# sch.net
KiCad netlist of a schematic drawn in EasyEDA
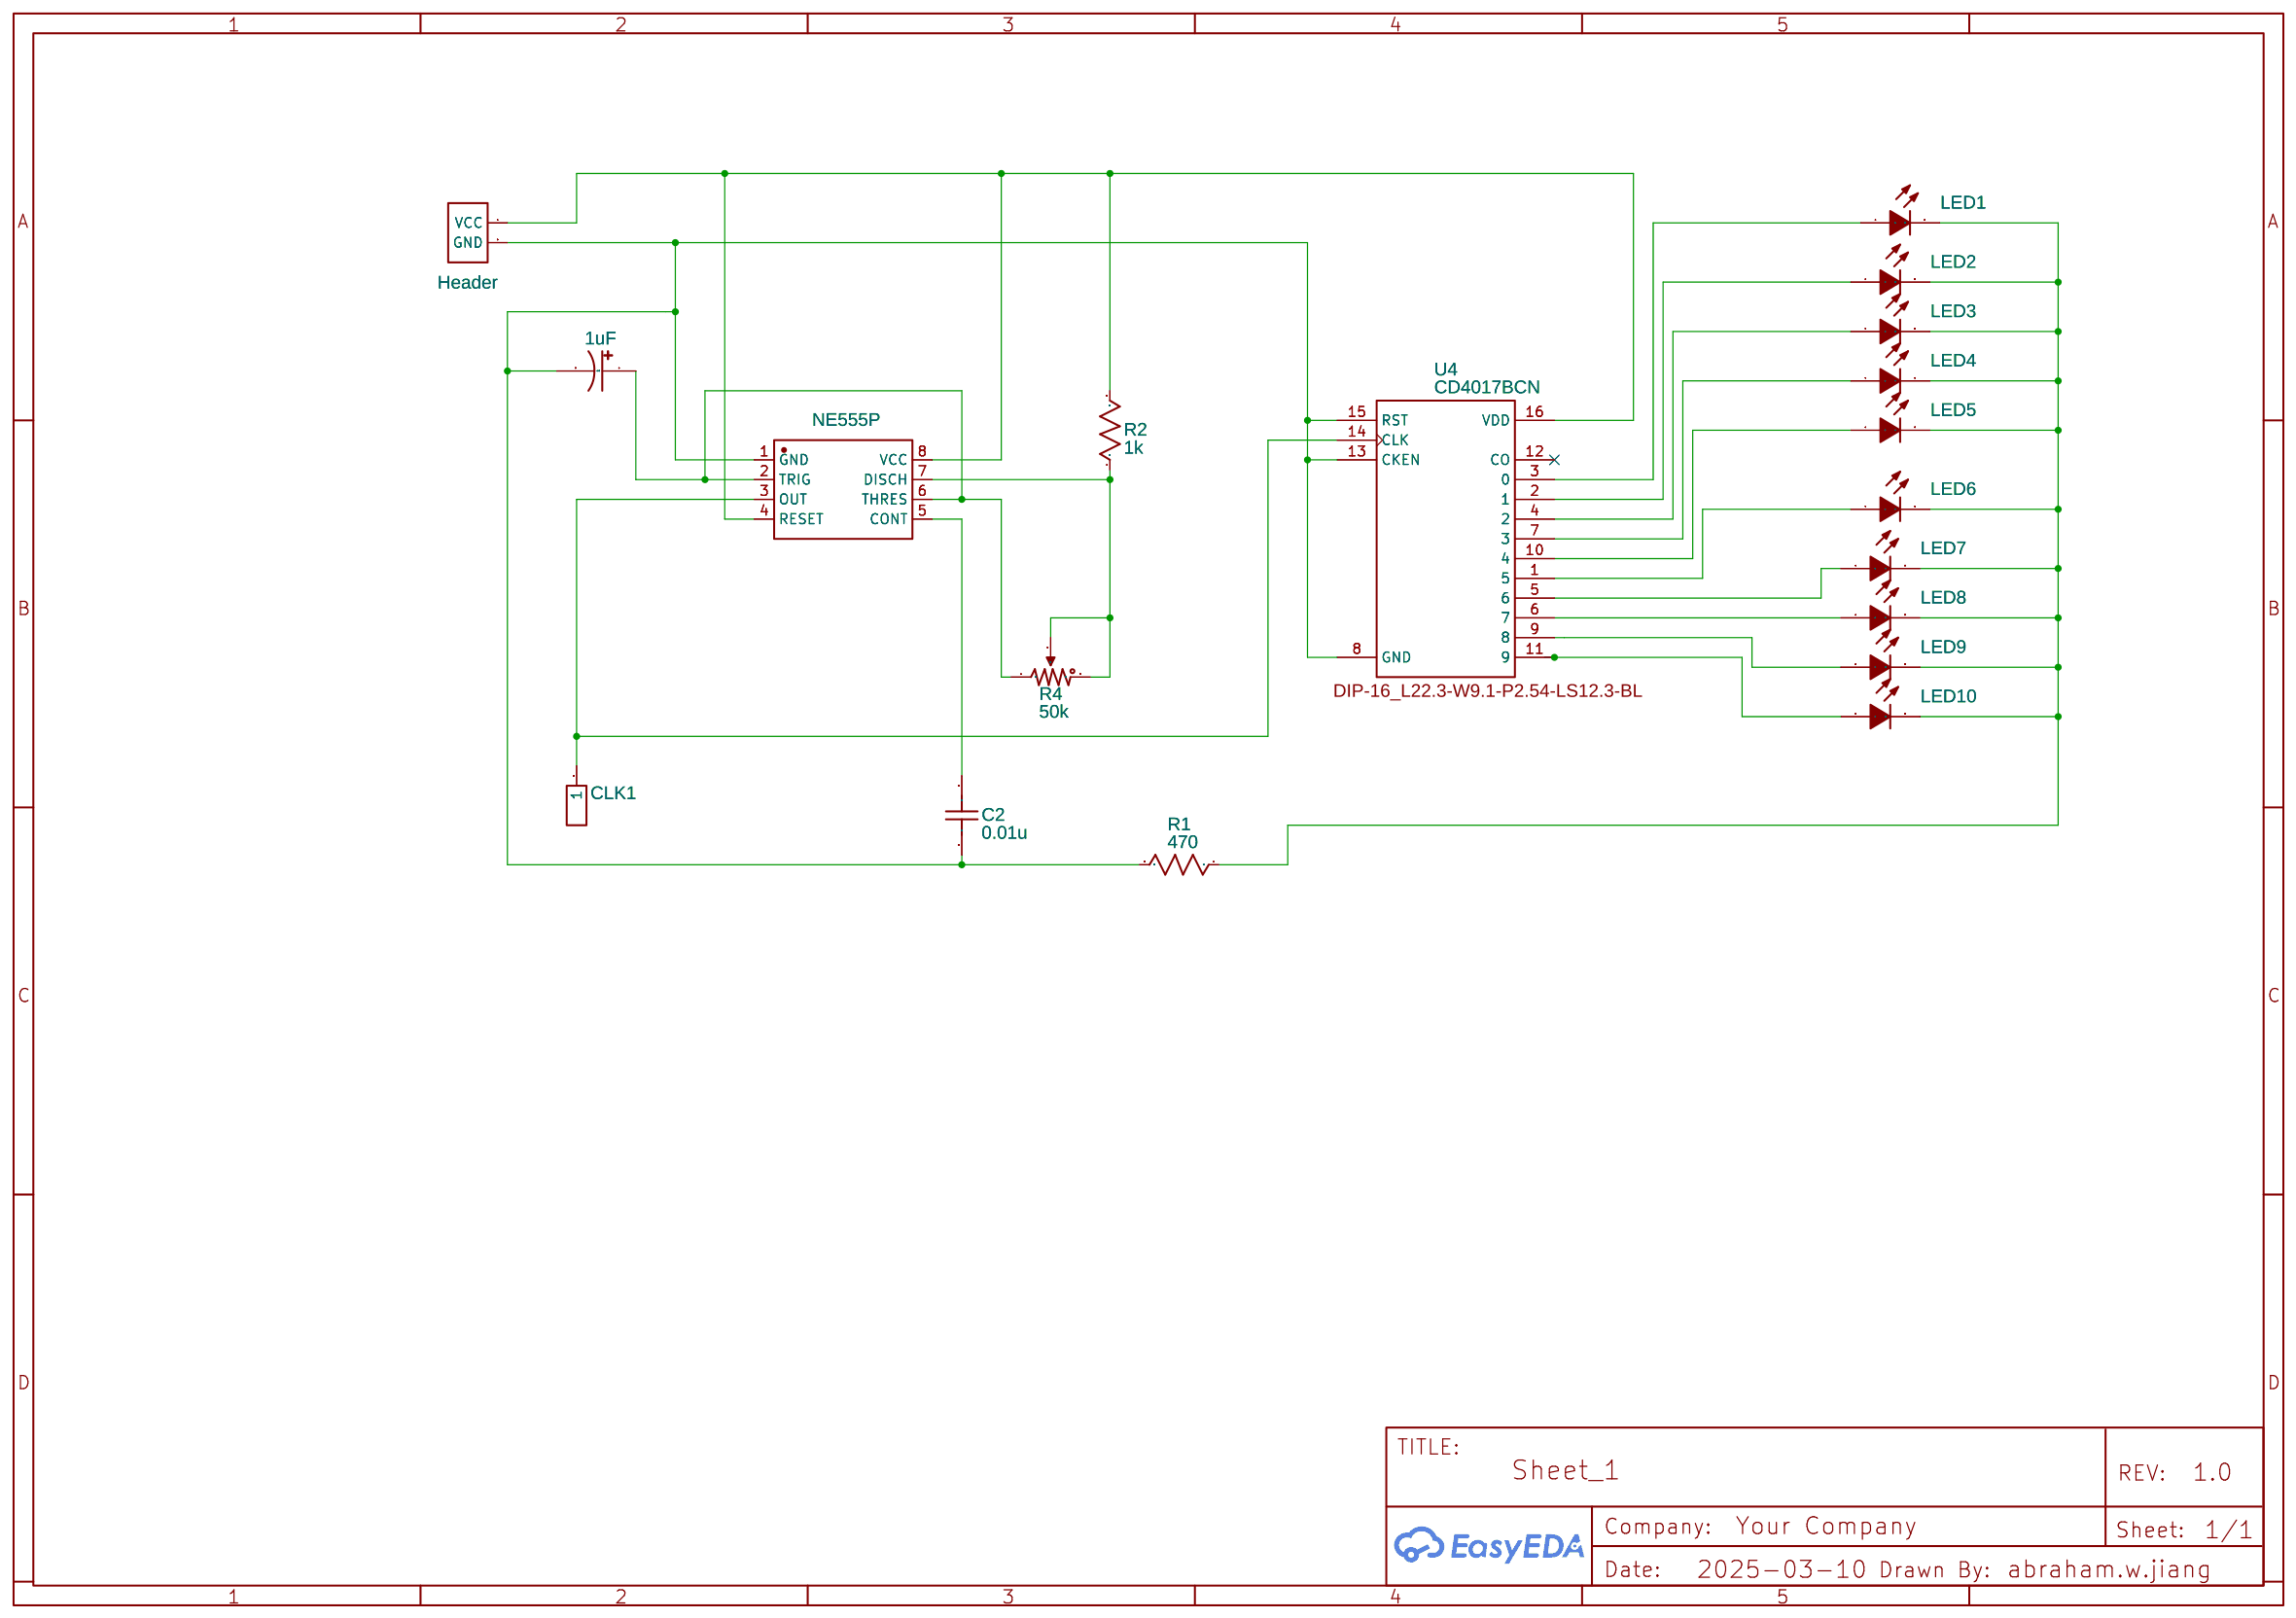
[diagram p0: schematic sheet]

(export (version "E")
  (design (tool "Eeschema 10.0.6"))
  (components
    (comp (ref "C1")
      (value "1uF")
      (fields (field (name "Manufacturer Part") "UVZ1H010MDD") (field (name "Manufacturer") "Nichicon(尼吉康)"))
      (libsource (lib "") (part "UVZ1H010MDD"))
    )
    (comp (ref "C2") (value "0.01u") (libsource (lib "") (part "C_0603_US")))
    (comp (ref "CLK1")
      (value "C81276")
      (fields
        (field (name "Manufacturer Part") "2.54-1*1P针")
        (field (name "Manufacturer") "BOOMELE(Boom Precision Elec)")
      )
      (libsource (lib "") (part "Header-Male-2.54_1x1"))
    )
    (comp (ref "H1") (value "Header") (libsource (lib "") (part "HEADER-FEMALE-2.54_1X2")))
    (comp (ref "LED1") (value "LED_5MM") (libsource (lib "") (part "LED_5MM")))
    (comp (ref "LED2") (value "LED_5MM") (libsource (lib "") (part "LED_5MM")))
    (comp (ref "LED3") (value "LED_5MM") (libsource (lib "") (part "LED_5MM")))
    (comp (ref "LED4") (value "LED_5MM") (libsource (lib "") (part "LED_5MM")))
    (comp (ref "LED5") (value "LED_5MM") (libsource (lib "") (part "LED_5MM")))
    (comp (ref "LED6") (value "LED_5MM") (libsource (lib "") (part "LED_5MM")))
    (comp (ref "LED7") (value "LED_5MM") (libsource (lib "") (part "LED_5MM")))
    (comp (ref "LED8") (value "LED_5MM") (libsource (lib "") (part "LED_5MM")))
    (comp (ref "LED9") (value "LED_5MM") (libsource (lib "") (part "LED_5MM")))
    (comp (ref "LED10") (value "LED_5MM") (libsource (lib "") (part "LED_5MM")))
    (comp (ref "R1")
      (value "470")
      (fields (field (name "Manufacturer Part") "?"))
      (libsource (lib "") (part "Resistor"))
    )
    (comp (ref "R2")
      (value "1k")
      (fields (field (name "Manufacturer Part") "?"))
      (libsource (lib "") (part "Resistor_1"))
    )
    (comp (ref "R4")
      (value "50k")
      (fields (field (name "Manufacturer Part") "?"))
      (libsource (lib "") (part "Potentiometer"))
    )
    (comp (ref "U2")
      (value "NE555P")
      (fields (field (name "Manufacturer") "TI(德州仪器)"))
      (libsource (lib "") (part "NE555P"))
    )
    (comp (ref "U4") (value "CD4017BCN") (libsource (lib "") (part "CD4017BCN")))
  )
  (nets
    (net (code "1") (name "Net-(H1-GND)") (class "Default")
      (node (ref "C1") (pin "2") (pinfunction "2_2") (pintype "unspecified"))
      (node (ref "C2") (pin "2") (pinfunction "2_2") (pintype "unspecified"))
      (node (ref "H1") (pin "2") (pinfunction "GND_2") (pintype "unspecified"))
      (node (ref "R1") (pin "2") (pinfunction "2_2") (pintype "unspecified"))
      (node (ref "U2") (pin "1") (pinfunction "GND_1") (pintype "unspecified"))
      (node (ref "U4") (pin "13") (pinfunction "CKEN_13") (pintype "unspecified"))
      (node (ref "U4") (pin "15") (pinfunction "RST_15") (pintype "unspecified"))
      (node (ref "U4") (pin "8") (pinfunction "GND_8") (pintype "passive"))
    )
    (net (code "2") (name "Net-(H1-VCC)") (class "Default")
      (node (ref "H1") (pin "1") (pinfunction "VCC_1") (pintype "unspecified"))
      (node (ref "R2") (pin "2") (pinfunction "2_2") (pintype "unspecified"))
      (node (ref "U2") (pin "4") (pinfunction "RESET_4") (pintype "unspecified"))
      (node (ref "U2") (pin "8") (pinfunction "VCC_8") (pintype "unspecified"))
      (node (ref "U4") (pin "16") (pinfunction "VDD_16") (pintype "passive"))
    )
    (net (code "3") (name "Net-(LED1-A)") (class "Default")
      (node (ref "LED1") (pin "1") (pinfunction "A_1") (pintype "input"))
      (node (ref "U4") (pin "3") (pinfunction "0_3") (pintype "output"))
    )
    (net (code "4") (name "Net-(LED1-K)") (class "Default")
      (node (ref "LED1") (pin "2") (pinfunction "K_2") (pintype "input"))
      (node (ref "LED10") (pin "2") (pinfunction "K_2") (pintype "input"))
      (node (ref "LED2") (pin "2") (pinfunction "K_2") (pintype "input"))
      (node (ref "LED3") (pin "2") (pinfunction "K_2") (pintype "input"))
      (node (ref "LED4") (pin "2") (pinfunction "K_2") (pintype "input"))
      (node (ref "LED5") (pin "2") (pinfunction "K_2") (pintype "input"))
      (node (ref "LED6") (pin "2") (pinfunction "K_2") (pintype "input"))
      (node (ref "LED7") (pin "2") (pinfunction "K_2") (pintype "input"))
      (node (ref "LED8") (pin "2") (pinfunction "K_2") (pintype "input"))
      (node (ref "LED9") (pin "2") (pinfunction "K_2") (pintype "input"))
      (node (ref "R1") (pin "1") (pinfunction "1_1") (pintype "unspecified"))
    )
    (net (code "5") (name "Net-(LED2-A)") (class "Default")
      (node (ref "LED2") (pin "1") (pinfunction "A_1") (pintype "input"))
      (node (ref "U4") (pin "2") (pinfunction "1_2") (pintype "output"))
    )
    (net (code "6") (name "Net-(LED3-A)") (class "Default")
      (node (ref "LED3") (pin "1") (pinfunction "A_1") (pintype "input"))
      (node (ref "U4") (pin "4") (pinfunction "2_4") (pintype "output"))
    )
    (net (code "7") (name "Net-(LED4-A)") (class "Default")
      (node (ref "LED4") (pin "1") (pinfunction "A_1") (pintype "input"))
      (node (ref "U4") (pin "7") (pinfunction "3_7") (pintype "output"))
    )
    (net (code "8") (name "Net-(LED5-A)") (class "Default")
      (node (ref "LED5") (pin "1") (pinfunction "A_1") (pintype "input"))
      (node (ref "U4") (pin "10") (pinfunction "4_10") (pintype "output"))
    )
    (net (code "9") (name "Net-(LED6-A)") (class "Default")
      (node (ref "LED6") (pin "1") (pinfunction "A_1") (pintype "input"))
      (node (ref "U4") (pin "1") (pinfunction "5_1") (pintype "output"))
    )
    (net (code "10") (name "Net-(LED7-A)") (class "Default")
      (node (ref "LED7") (pin "1") (pinfunction "A_1") (pintype "input"))
      (node (ref "U4") (pin "5") (pinfunction "6_5") (pintype "output"))
    )
    (net (code "11") (name "Net-(LED8-A)") (class "Default")
      (node (ref "LED8") (pin "1") (pinfunction "A_1") (pintype "input"))
      (node (ref "U4") (pin "6") (pinfunction "7_6") (pintype "output"))
    )
    (net (code "12") (name "Net-(LED9-A)") (class "Default")
      (node (ref "LED9") (pin "1") (pinfunction "A_1") (pintype "input"))
      (node (ref "U4") (pin "9") (pinfunction "8_9") (pintype "output"))
    )
    (net (code "13") (name "Net-(LED10-A)") (class "Default")
      (node (ref "LED10") (pin "1") (pinfunction "A_1") (pintype "input"))
      (node (ref "U4") (pin "11") (pinfunction "9_11") (pintype "output"))
    )
    (net (code "14") (name "Net-(R4-2)") (class "Default")
      (node (ref "R2") (pin "1") (pinfunction "1_1") (pintype "unspecified"))
      (node (ref "R4") (pin "2") (pinfunction "3_2") (pintype "unspecified"))
      (node (ref "R4") (pin "3") (pinfunction "2_3") (pintype "unspecified"))
      (node (ref "U2") (pin "7") (pinfunction "DISCH_7") (pintype "unspecified"))
    )
    (net (code "15") (name "Net-(U2-CONT)") (class "Default")
      (node (ref "C2") (pin "1") (pinfunction "1_1") (pintype "unspecified"))
      (node (ref "U2") (pin "5") (pinfunction "CONT_5") (pintype "unspecified"))
    )
    (net (code "16") (name "Net-(U2-OUT)") (class "Default")
      (node (ref "CLK1") (pin "1") (pinfunction "1_1") (pintype "unspecified"))
      (node (ref "U2") (pin "3") (pinfunction "OUT_3") (pintype "unspecified"))
      (node (ref "U4") (pin "14") (pinfunction "CLK_14") (pintype "unspecified"))
    )
    (net (code "17") (name "Net-(U2-THRES)") (class "Default")
      (node (ref "C1") (pin "1") (pinfunction "1_1") (pintype "unspecified"))
      (node (ref "R4") (pin "1") (pinfunction "1_1") (pintype "unspecified"))
      (node (ref "U2") (pin "2") (pinfunction "TRIG_2") (pintype "unspecified"))
      (node (ref "U2") (pin "6") (pinfunction "THRES_6") (pintype "unspecified"))
    )
    (net (code "18") (name "unconnected-(U4-CO-Pad12)") (class "Default")
      (node (ref "U4") (pin "12") (pinfunction "CO_12") (pintype "output+no_connect"))
    )
  )
)
